# board_3.net
KiCad netlist of a schematic drawn in EAGLE
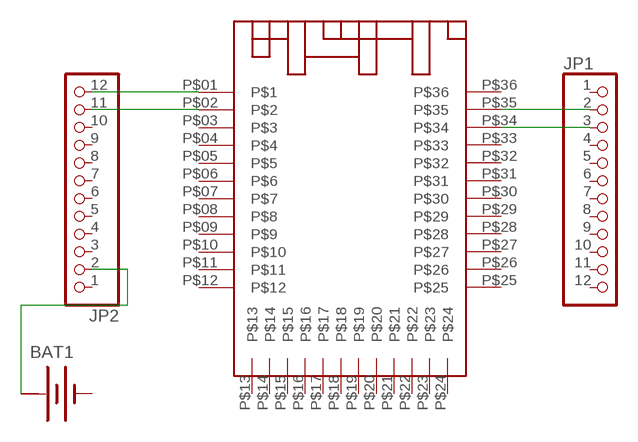
[diagram p0: schematic, sheet 1]

(export (version "E")
  (design (tool "Eeschema 10.0.6"))
  (components
    (comp (ref "BAT1")
      (value "BATTERY")
      (footprint "eagle-import:BATTERY")
      (libsource (lib "eagle-import") (part "BATTERY"))
    )
    (comp (ref "JP1")
      (value "PINHD-1X12")
      (footprint "eagle-import:1X12")
      (libsource (lib "eagle-import") (part "PINHD-1X12"))
    )
    (comp (ref "JP2")
      (value "PINHD-1X12/90")
      (footprint "eagle-import:1X12_90")
      (libsource (lib "eagle-import") (part "PINHD-1X12/90"))
    )
    (comp (ref "U$1")
      (value "HZX_MODULE")
      (footprint "eagle-import:SMD_PAD_VERSION")
      (fields (field (name "AUTHOR") "Agam"))
      (libsource (lib "eagle-import") (part "HZX_MODULE"))
    )
  )
  (nets
    (net (code "1") (name "/+") (class "Default")
      (node (ref "BAT1") (pin "+@1") (pinfunction "+_+@1") (pintype "power_in"))
    )
    (net (code "2") (name "/-") (class "Default")
      (node (ref "BAT1") (pin "-") (pinfunction "-_-") (pintype "power_in"))
    )
    (net (code "3") (name "Net-(BAT1-Pad+)") (class "Default")
      (node (ref "BAT1") (pin "+") (pinfunction "+_+") (pintype "power_in"))
      (node (ref "JP2") (pin "2") (pinfunction "2_2") (pintype "passive"))
    )
    (net (code "4") (name "Net-(JP1-Pad2)") (class "Default")
      (node (ref "JP1") (pin "2") (pinfunction "2_2") (pintype "passive"))
      (node (ref "U$1") (pin "P$35") (pinfunction "P$35_P$35") (pintype "bidirectional"))
    )
    (net (code "5") (name "Net-(JP1-Pad3)") (class "Default")
      (node (ref "JP1") (pin "3") (pinfunction "3_3") (pintype "passive"))
      (node (ref "U$1") (pin "P$34") (pinfunction "P$34_P$34") (pintype "bidirectional"))
    )
    (net (code "6") (name "Net-(U$1-P$1)") (class "Default")
      (node (ref "JP2") (pin "12") (pinfunction "12_12") (pintype "passive"))
      (node (ref "U$1") (pin "P$01") (pinfunction "P$1_P$01") (pintype "bidirectional"))
    )
    (net (code "7") (name "Net-(U$1-P$2)") (class "Default")
      (node (ref "JP2") (pin "11") (pinfunction "11_11") (pintype "passive"))
      (node (ref "U$1") (pin "P$02") (pinfunction "P$2_P$02") (pintype "bidirectional"))
    )
    (net (code "8") (name "unconnected-(JP1-Pad1)") (class "Default")
      (node (ref "JP1") (pin "1") (pinfunction "1_1") (pintype "passive"))
    )
    (net (code "9") (name "unconnected-(JP1-Pad4)") (class "Default")
      (node (ref "JP1") (pin "4") (pinfunction "4_4") (pintype "passive"))
    )
    (net (code "10") (name "unconnected-(JP1-Pad5)") (class "Default")
      (node (ref "JP1") (pin "5") (pinfunction "5_5") (pintype "passive"))
    )
    (net (code "11") (name "unconnected-(JP1-Pad6)") (class "Default")
      (node (ref "JP1") (pin "6") (pinfunction "6_6") (pintype "passive"))
    )
    (net (code "12") (name "unconnected-(JP1-Pad7)") (class "Default")
      (node (ref "JP1") (pin "7") (pinfunction "7_7") (pintype "passive"))
    )
    (net (code "13") (name "unconnected-(JP1-Pad8)") (class "Default")
      (node (ref "JP1") (pin "8") (pinfunction "8_8") (pintype "passive"))
    )
    (net (code "14") (name "unconnected-(JP1-Pad9)") (class "Default")
      (node (ref "JP1") (pin "9") (pinfunction "9_9") (pintype "passive"))
    )
    (net (code "15") (name "unconnected-(JP1-Pad10)") (class "Default")
      (node (ref "JP1") (pin "10") (pinfunction "10_10") (pintype "passive"))
    )
    (net (code "16") (name "unconnected-(JP1-Pad11)") (class "Default")
      (node (ref "JP1") (pin "11") (pinfunction "11_11") (pintype "passive"))
    )
    (net (code "17") (name "unconnected-(JP1-Pad12)") (class "Default")
      (node (ref "JP1") (pin "12") (pinfunction "12_12") (pintype "passive"))
    )
    (net (code "18") (name "unconnected-(JP2-Pad1)") (class "Default")
      (node (ref "JP2") (pin "1") (pinfunction "1_1") (pintype "passive"))
    )
    (net (code "19") (name "unconnected-(JP2-Pad3)") (class "Default")
      (node (ref "JP2") (pin "3") (pinfunction "3_3") (pintype "passive"))
    )
    (net (code "20") (name "unconnected-(JP2-Pad4)") (class "Default")
      (node (ref "JP2") (pin "4") (pinfunction "4_4") (pintype "passive"))
    )
    (net (code "21") (name "unconnected-(JP2-Pad5)") (class "Default")
      (node (ref "JP2") (pin "5") (pinfunction "5_5") (pintype "passive"))
    )
    (net (code "22") (name "unconnected-(JP2-Pad6)") (class "Default")
      (node (ref "JP2") (pin "6") (pinfunction "6_6") (pintype "passive"))
    )
    (net (code "23") (name "unconnected-(JP2-Pad7)") (class "Default")
      (node (ref "JP2") (pin "7") (pinfunction "7_7") (pintype "passive"))
    )
    (net (code "24") (name "unconnected-(JP2-Pad8)") (class "Default")
      (node (ref "JP2") (pin "8") (pinfunction "8_8") (pintype "passive"))
    )
    (net (code "25") (name "unconnected-(JP2-Pad9)") (class "Default")
      (node (ref "JP2") (pin "9") (pinfunction "9_9") (pintype "passive"))
    )
    (net (code "26") (name "unconnected-(JP2-Pad10)") (class "Default")
      (node (ref "JP2") (pin "10") (pinfunction "10_10") (pintype "passive"))
    )
    (net (code "27") (name "unconnected-(U$1-P$3-PadP$03)") (class "Default")
      (node (ref "U$1") (pin "P$03") (pinfunction "P$3_P$03") (pintype "bidirectional"))
    )
    (net (code "28") (name "unconnected-(U$1-P$4-PadP$04)") (class "Default")
      (node (ref "U$1") (pin "P$04") (pinfunction "P$4_P$04") (pintype "bidirectional"))
    )
    (net (code "29") (name "unconnected-(U$1-P$5-PadP$05)") (class "Default")
      (node (ref "U$1") (pin "P$05") (pinfunction "P$5_P$05") (pintype "bidirectional"))
    )
    (net (code "30") (name "unconnected-(U$1-P$6-PadP$06)") (class "Default")
      (node (ref "U$1") (pin "P$06") (pinfunction "P$6_P$06") (pintype "bidirectional"))
    )
    (net (code "31") (name "unconnected-(U$1-P$7-PadP$07)") (class "Default")
      (node (ref "U$1") (pin "P$07") (pinfunction "P$7_P$07") (pintype "bidirectional"))
    )
    (net (code "32") (name "unconnected-(U$1-P$8-PadP$08)") (class "Default")
      (node (ref "U$1") (pin "P$08") (pinfunction "P$8_P$08") (pintype "bidirectional"))
    )
    (net (code "33") (name "unconnected-(U$1-P$9-PadP$09)") (class "Default")
      (node (ref "U$1") (pin "P$09") (pinfunction "P$9_P$09") (pintype "bidirectional"))
    )
    (net (code "34") (name "unconnected-(U$1-PadP$10)") (class "Default")
      (node (ref "U$1") (pin "P$10") (pinfunction "P$10_P$10") (pintype "bidirectional"))
    )
    (net (code "35") (name "unconnected-(U$1-PadP$11)") (class "Default")
      (node (ref "U$1") (pin "P$11") (pinfunction "P$11_P$11") (pintype "bidirectional"))
    )
    (net (code "36") (name "unconnected-(U$1-PadP$12)") (class "Default")
      (node (ref "U$1") (pin "P$12") (pinfunction "P$12_P$12") (pintype "bidirectional"))
    )
    (net (code "37") (name "unconnected-(U$1-PadP$13)") (class "Default")
      (node (ref "U$1") (pin "P$13") (pinfunction "P$13_P$13") (pintype "bidirectional"))
    )
    (net (code "38") (name "unconnected-(U$1-PadP$14)") (class "Default")
      (node (ref "U$1") (pin "P$14") (pinfunction "P$14_P$14") (pintype "bidirectional"))
    )
    (net (code "39") (name "unconnected-(U$1-PadP$15)") (class "Default")
      (node (ref "U$1") (pin "P$15") (pinfunction "P$15_P$15") (pintype "bidirectional"))
    )
    (net (code "40") (name "unconnected-(U$1-PadP$16)") (class "Default")
      (node (ref "U$1") (pin "P$16") (pinfunction "P$16_P$16") (pintype "bidirectional"))
    )
    (net (code "41") (name "unconnected-(U$1-PadP$17)") (class "Default")
      (node (ref "U$1") (pin "P$17") (pinfunction "P$17_P$17") (pintype "bidirectional"))
    )
    (net (code "42") (name "unconnected-(U$1-PadP$18)") (class "Default")
      (node (ref "U$1") (pin "P$18") (pinfunction "P$18_P$18") (pintype "bidirectional"))
    )
    (net (code "43") (name "unconnected-(U$1-PadP$19)") (class "Default")
      (node (ref "U$1") (pin "P$19") (pinfunction "P$19_P$19") (pintype "bidirectional"))
    )
    (net (code "44") (name "unconnected-(U$1-PadP$20)") (class "Default")
      (node (ref "U$1") (pin "P$20") (pinfunction "P$20_P$20") (pintype "bidirectional"))
    )
    (net (code "45") (name "unconnected-(U$1-PadP$21)") (class "Default")
      (node (ref "U$1") (pin "P$21") (pinfunction "P$21_P$21") (pintype "bidirectional"))
    )
    (net (code "46") (name "unconnected-(U$1-PadP$22)") (class "Default")
      (node (ref "U$1") (pin "P$22") (pinfunction "P$22_P$22") (pintype "bidirectional"))
    )
    (net (code "47") (name "unconnected-(U$1-PadP$23)") (class "Default")
      (node (ref "U$1") (pin "P$23") (pinfunction "P$23_P$23") (pintype "bidirectional"))
    )
    (net (code "48") (name "unconnected-(U$1-PadP$24)") (class "Default")
      (node (ref "U$1") (pin "P$24") (pinfunction "P$24_P$24") (pintype "bidirectional"))
    )
    (net (code "49") (name "unconnected-(U$1-PadP$25)") (class "Default")
      (node (ref "U$1") (pin "P$25") (pinfunction "P$25_P$25") (pintype "bidirectional"))
    )
    (net (code "50") (name "unconnected-(U$1-PadP$26)") (class "Default")
      (node (ref "U$1") (pin "P$26") (pinfunction "P$26_P$26") (pintype "bidirectional"))
    )
    (net (code "51") (name "unconnected-(U$1-PadP$27)") (class "Default")
      (node (ref "U$1") (pin "P$27") (pinfunction "P$27_P$27") (pintype "bidirectional"))
    )
    (net (code "52") (name "unconnected-(U$1-PadP$28)") (class "Default")
      (node (ref "U$1") (pin "P$28") (pinfunction "P$28_P$28") (pintype "bidirectional"))
    )
    (net (code "53") (name "unconnected-(U$1-PadP$29)") (class "Default")
      (node (ref "U$1") (pin "P$29") (pinfunction "P$29_P$29") (pintype "bidirectional"))
    )
    (net (code "54") (name "unconnected-(U$1-PadP$30)") (class "Default")
      (node (ref "U$1") (pin "P$30") (pinfunction "P$30_P$30") (pintype "bidirectional"))
    )
    (net (code "55") (name "unconnected-(U$1-PadP$31)") (class "Default")
      (node (ref "U$1") (pin "P$31") (pinfunction "P$31_P$31") (pintype "bidirectional"))
    )
    (net (code "56") (name "unconnected-(U$1-PadP$32)") (class "Default")
      (node (ref "U$1") (pin "P$32") (pinfunction "P$32_P$32") (pintype "bidirectional"))
    )
    (net (code "57") (name "unconnected-(U$1-PadP$33)") (class "Default")
      (node (ref "U$1") (pin "P$33") (pinfunction "P$33_P$33") (pintype "bidirectional"))
    )
    (net (code "58") (name "unconnected-(U$1-PadP$36)") (class "Default")
      (node (ref "U$1") (pin "P$36") (pinfunction "P$36_P$36") (pintype "bidirectional"))
    )
  )
)
